# LimitSwitch.net
KiCad netlist of a schematic drawn in EAGLE
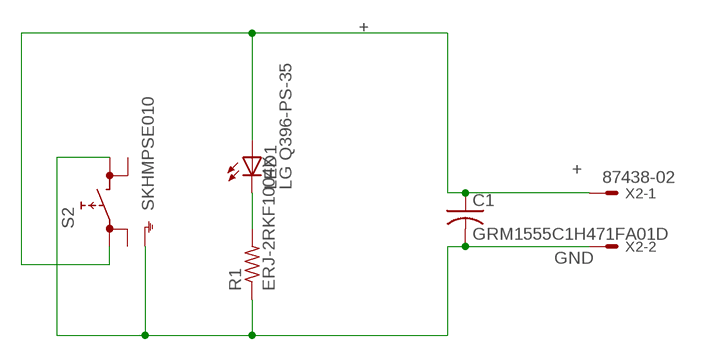
[diagram p0: schematic, sheet 1]

(export (version "E")
  (design (tool "Eeschema 10.0.6"))
  (components
    (comp (ref "C1")
      (value "GRM1555C1H471FA01D")
      (footprint "eagle-import:C0402")
      (libsource (lib "eagle-import") (part "C-USC0402"))
    )
    (comp (ref "LED1")
      (value "LG Q396-PS-35")
      (footprint "eagle-import:CHIPLED_0603")
      (libsource (lib "eagle-import") (part "LEDCHIPLED_0603"))
    )
    (comp (ref "R1")
      (value "ERJ-2RKF1004X")
      (footprint "eagle-import:R0402")
      (libsource (lib "eagle-import") (part "R-US_R0402"))
    )
    (comp (ref "S2")
      (value "SKHMPSE010")
      (footprint "eagle-import:SKHMPXE010")
      (libsource (lib "eagle-import") (part "SKHMPE010S"))
    )
    (comp (ref "X2")
      (value "87438-02")
      (footprint "eagle-import:87438-02")
      (libsource (lib "eagle-import") (part "87438-02"))
    )
  )
  (nets
    (net (code "1") (name "/+") (class "Default")
      (node (ref "C1") (pin "1") (pinfunction "1_1") (pintype "passive"))
      (node (ref "LED1") (pin "A") (pinfunction "A_A") (pintype "passive"))
      (node (ref "S2") (pin "1") (pinfunction "1.1_1") (pintype "passive"))
      (node (ref "X2") (pin "1") (pinfunction "S_1") (pintype "passive"))
    )
    (net (code "2") (name "/GND") (class "Default")
      (node (ref "C1") (pin "2") (pinfunction "2_2") (pintype "passive"))
      (node (ref "R1") (pin "1") (pinfunction "1_1") (pintype "passive"))
      (node (ref "S2") (pin "3") (pinfunction "2.1_3") (pintype "passive"))
      (node (ref "S2") (pin "5") (pinfunction "SH_5") (pintype "passive"))
      (node (ref "X2") (pin "2") (pinfunction "S_2") (pintype "passive"))
    )
    (net (code "3") (name "Net-(LED1-PadC)") (class "Default")
      (node (ref "LED1") (pin "C") (pinfunction "C_C") (pintype "passive"))
      (node (ref "R1") (pin "2") (pinfunction "2_2") (pintype "passive"))
    )
    (net (code "4") (name "unconnected-(S2-1.2-Pad2)") (class "Default")
      (node (ref "S2") (pin "2") (pinfunction "1.2_2") (pintype "passive"))
    )
    (net (code "5") (name "unconnected-(S2-2.2-Pad4)") (class "Default")
      (node (ref "S2") (pin "4") (pinfunction "2.2_4") (pintype "passive"))
    )
  )
)
